# untitled.net
KiCad netlist of a schematic drawn in EAGLE
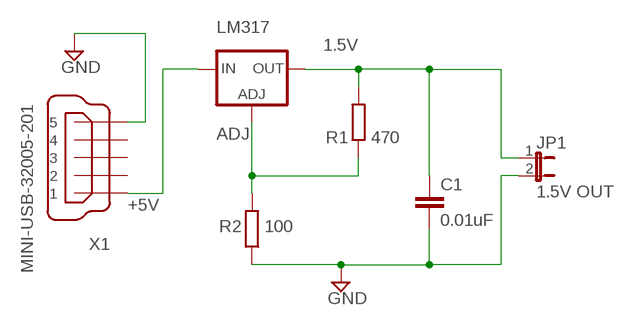
[diagram p0: schematic, sheet 1]

(export (version "E")
  (design (tool "Eeschema 10.0.6"))
  (components
    (comp (ref "C1")
      (value "0.01uF")
      (footprint "eagle-import:C050-025X075")
      (libsource (lib "eagle-import") (part "C-EU050-025X075"))
    )
    (comp (ref "JP1")
      (value "1.5V OUT")
      (footprint "eagle-import:JP1")
      (libsource (lib "eagle-import") (part "JP1E"))
    )
    (comp (ref "LM317")
      (value "LM317TL")
      (footprint "eagle-import:317TL")
      (libsource (lib "eagle-import") (part "LM317TL"))
    )
    (comp (ref "R1")
      (value "470")
      (footprint "eagle-import:0204_7")
      (libsource (lib "eagle-import") (part "R-EU_0204/7"))
    )
    (comp (ref "R2")
      (value "100")
      (footprint "eagle-import:0204_7")
      (libsource (lib "eagle-import") (part "R-EU_0204/7"))
    )
    (comp (ref "X1")
      (value "MINI-USB-32005-201")
      (footprint "eagle-import:32005-201")
      (libsource (lib "eagle-import") (part "MINI-USB-32005-201"))
    )
  )
  (nets
    (net (code "1") (name "/+5V") (class "Default")
      (node (ref "LM317") (pin "3") (pinfunction "IN_3") (pintype "input"))
      (node (ref "X1") (pin "1") (pinfunction "1_1") (pintype "passive"))
    )
    (net (code "2") (name "/1.5V") (class "Default")
      (node (ref "C1") (pin "1") (pinfunction "1_1") (pintype "passive"))
      (node (ref "JP1") (pin "1") (pinfunction "1_1") (pintype "passive"))
      (node (ref "LM317") (pin "2") (pinfunction "OUT_2") (pintype "passive"))
      (node (ref "R1") (pin "2") (pinfunction "2_2") (pintype "passive"))
    )
    (net (code "3") (name "/ADJ") (class "Default")
      (node (ref "LM317") (pin "1") (pinfunction "ADJ_1") (pintype "input"))
      (node (ref "R1") (pin "1") (pinfunction "1_1") (pintype "passive"))
      (node (ref "R2") (pin "2") (pinfunction "2_2") (pintype "passive"))
    )
    (net (code "4") (name "GND") (class "Default")
      (node (ref "C1") (pin "2") (pinfunction "2_2") (pintype "passive"))
      (node (ref "JP1") (pin "2") (pinfunction "2_2") (pintype "passive"))
      (node (ref "R2") (pin "1") (pinfunction "1_1") (pintype "passive"))
      (node (ref "X1") (pin "5") (pinfunction "5_5") (pintype "passive"))
    )
    (net (code "5") (name "unconnected-(X1-Pad2)") (class "Default")
      (node (ref "X1") (pin "2") (pinfunction "2_2") (pintype "passive"))
    )
    (net (code "6") (name "unconnected-(X1-Pad3)") (class "Default")
      (node (ref "X1") (pin "3") (pinfunction "3_3") (pintype "passive"))
    )
    (net (code "7") (name "unconnected-(X1-Pad4)") (class "Default")
      (node (ref "X1") (pin "4") (pinfunction "4_4") (pintype "passive"))
    )
  )
)
